# PowerInput.net
KiCad netlist of a schematic drawn in Altium Designer
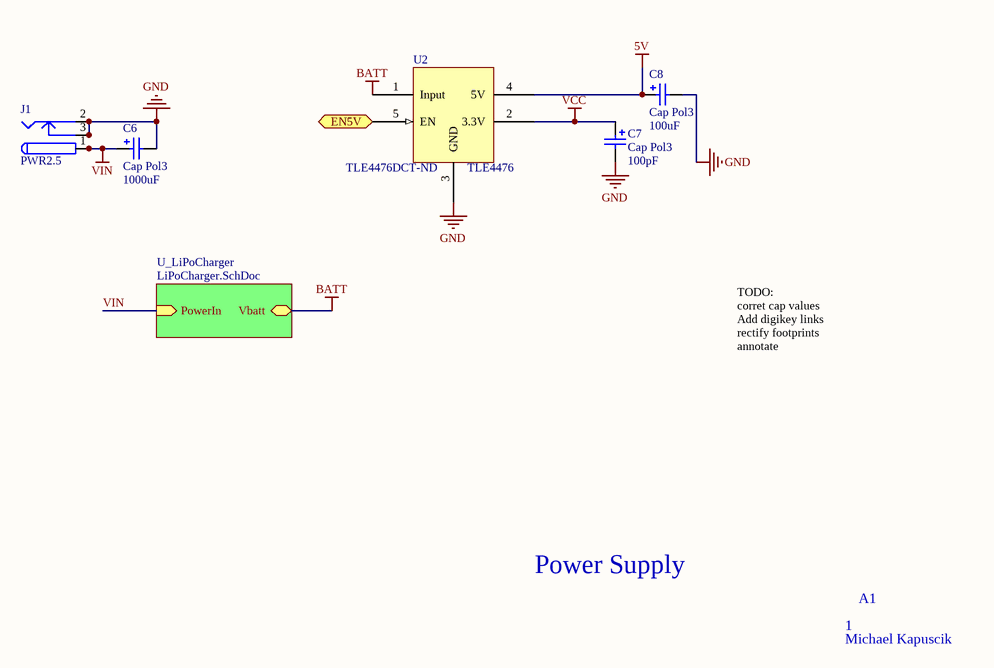
[diagram p0: PowerInput.SchDoc]

(export (version "E")
  (design (tool "Eeschema 10.0.6"))
  (components
    (comp (ref "C6")
      (value "Cap Pol3")
      (footprint "C2225")
      (description "Polarized Capacitor (Surface Mount)")
      (fields (field (name "ALTIUM_VALUE") "1000uF") (field (name "PUBLISHER") "Altium Limited"))
      (libsource (lib "Miscellaneous Devices") (part "Cap Pol3"))
    )
    (comp (ref "C7")
      (value "Cap Pol3")
      (footprint "C2225")
      (description "Polarized Capacitor (Surface Mount)")
      (fields (field (name "ALTIUM_VALUE") "100pF") (field (name "PUBLISHER") "Altium Limited"))
      (libsource (lib "Miscellaneous Devices") (part "Cap Pol3"))
    )
    (comp (ref "C8")
      (value "Cap Pol3")
      (footprint "C2225")
      (description "Polarized Capacitor (Surface Mount)")
      (fields (field (name "ALTIUM_VALUE") "100uF") (field (name "PUBLISHER") "Altium Limited"))
      (libsource (lib "Miscellaneous Devices") (part "Cap Pol3"))
    )
    (comp (ref "J1")
      (value "PWR2.5")
      (footprint "KLD-0202")
      (description "Low Voltage Power Supply Connector")
      (fields (field (name "PUBLISHER") "Altium Limited"))
      (libsource (lib "Miscellaneous Connectors") (part "PWR2.5"))
    )
    (comp (ref "U2")
      (value "TLE4476")
      (footprint "P-TO252-5-1")
      (fields (field (name "SUPPLIER PART NUMBER 1") "TLE4476DCT-ND"))
      (libsource (lib "Miscellaneous Devices") (part "TLE4476"))
    )
  )
  (nets
    (net (code "1") (name "/EN5V") (class "Default")
      (node (ref "U2") (pin "5") (pinfunction "EN_5") (pintype "input"))
    )
    (net (code "2") (name "5V") (class "Default")
      (node (ref "C8") (pin "1") (pinfunction "1_1") (pintype "passive"))
      (node (ref "U2") (pin "4") (pinfunction "5V_4") (pintype "power_in"))
    )
    (net (code "3") (name "BATT") (class "Default")
      (node (ref "U2") (pin "1") (pinfunction "Input_1") (pintype "power_in"))
    )
    (net (code "4") (name "GND") (class "Default")
      (node (ref "C6") (pin "2") (pinfunction "2_2") (pintype "passive"))
      (node (ref "C7") (pin "2") (pinfunction "2_2") (pintype "passive"))
      (node (ref "C8") (pin "2") (pinfunction "2_2") (pintype "passive"))
      (node (ref "J1") (pin "2") (pinfunction "2_2") (pintype "power_in"))
      (node (ref "J1") (pin "2A") (pinfunction "2A_2A") (pintype "power_in"))
      (node (ref "J1") (pin "2B") (pinfunction "2B_2B") (pintype "power_in"))
      (node (ref "J1") (pin "3") (pinfunction "3_3") (pintype "power_in"))
      (node (ref "J1") (pin "3A") (pinfunction "3A_3A") (pintype "power_in"))
      (node (ref "J1") (pin "3B") (pinfunction "3B_3B") (pintype "power_in"))
      (node (ref "U2") (pin "3") (pinfunction "GND_3") (pintype "power_in"))
    )
    (net (code "5") (name "VCC") (class "Default")
      (node (ref "C7") (pin "1") (pinfunction "1_1") (pintype "passive"))
      (node (ref "U2") (pin "2") (pinfunction "3.3V_2") (pintype "power_in"))
    )
    (net (code "6") (name "VIN") (class "Default")
      (node (ref "C6") (pin "1") (pinfunction "1_1") (pintype "passive"))
      (node (ref "J1") (pin "1") (pinfunction "1_1") (pintype "power_in"))
      (node (ref "J1") (pin "1A") (pinfunction "1A_1A") (pintype "power_in"))
      (node (ref "J1") (pin "1B") (pinfunction "1B_1B") (pintype "power_in"))
    )
  )
)
